# SFD-V1.net
KiCad netlist of a schematic drawn in EAGLE
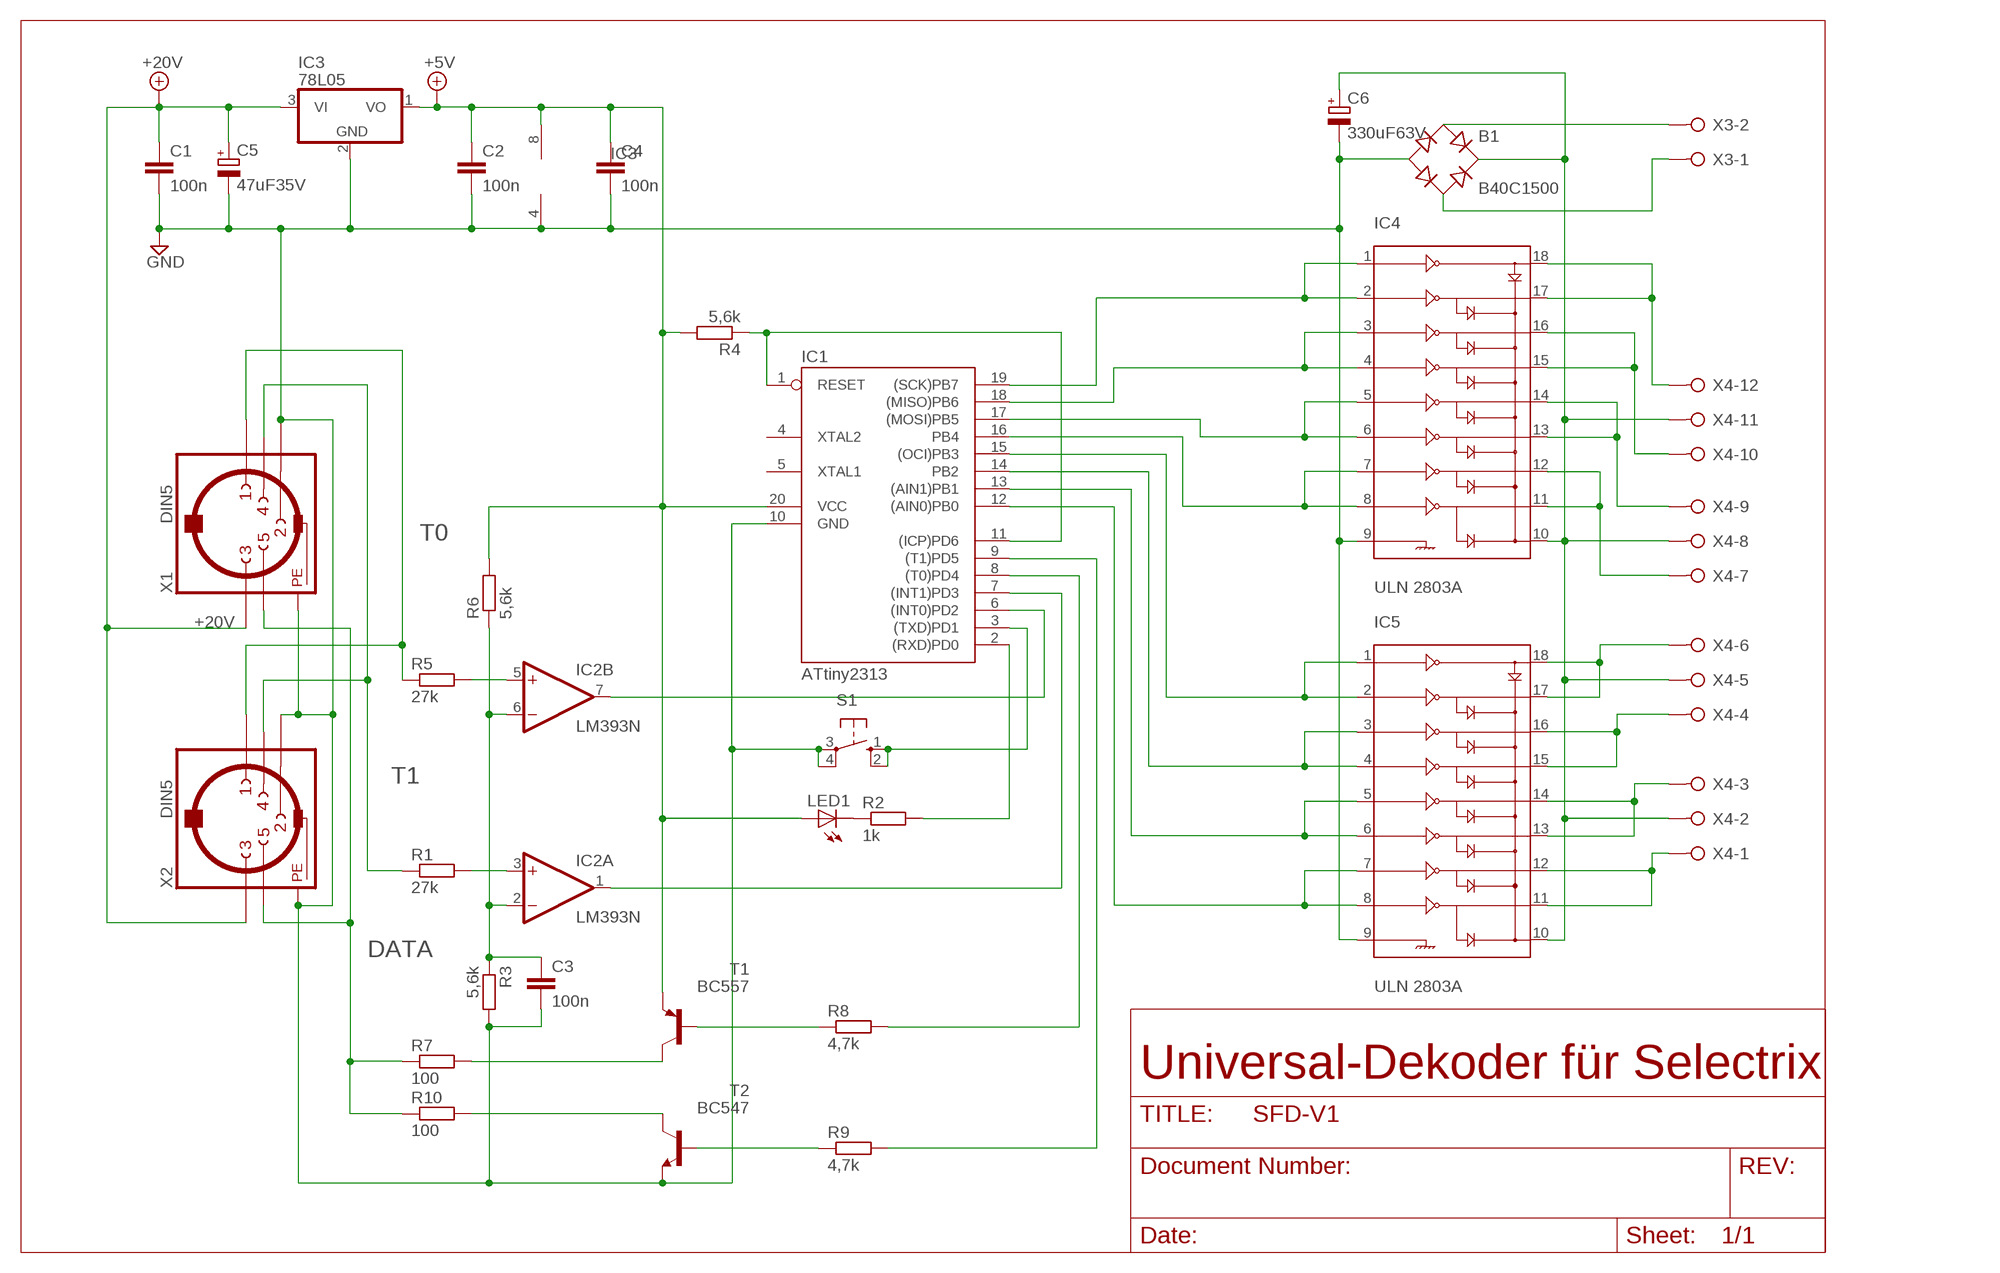
[diagram p0: schematic, sheet 1]

(export (version "E")
  (design (tool "Eeschema 10.0.6"))
  (components
    (comp (ref "B1")
      (value "B40C1500")
      (footprint "eagle-import:RB1A")
      (libsource (lib "eagle-import") (part "RECTIFIER-RB1A"))
    )
    (comp (ref "C1")
      (value "100n")
      (footprint "eagle-import:C025-025X050")
      (libsource (lib "eagle-import") (part "C-EU025-025X050"))
    )
    (comp (ref "C2")
      (value "100n")
      (footprint "eagle-import:C025-025X050")
      (libsource (lib "eagle-import") (part "C-EU025-025X050"))
    )
    (comp (ref "C3")
      (value "100n")
      (footprint "eagle-import:C025-025X050")
      (libsource (lib "eagle-import") (part "C-EU025-025X050"))
    )
    (comp (ref "C4")
      (value "100n")
      (footprint "eagle-import:C025-025X050")
      (libsource (lib "eagle-import") (part "C-EU025-025X050"))
    )
    (comp (ref "C5")
      (value "47uF35V")
      (footprint "eagle-import:E2,5-6E")
      (libsource (lib "eagle-import") (part "CPOL-EUE2,5-6E"))
    )
    (comp (ref "C6")
      (value "330uF63V")
      (footprint "eagle-import:E5-13")
      (libsource (lib "eagle-import") (part "rcl_334_CPOL-EUE5-13"))
    )
    (comp (ref "IC1")
      (value "ATtiny2313")
      (footprint "eagle-import:DIL20")
      (libsource (lib "eagle-import") (part "AT90S2313P"))
    )
    (comp (ref "IC2")
      (value "LM393N")
      (footprint "eagle-import:DIL08")
      (libsource (lib "eagle-import") (part "LM393N"))
    )
    (comp (ref "IC3")
      (value "78L05")
      (footprint "eagle-import:TO92")
      (libsource (lib "eagle-import") (part "78ZL05"))
    )
    (comp (ref "IC4")
      (value "ULN 2803A")
      (footprint "eagle-import:DIL18")
      (libsource (lib "eagle-import") (part "ULN2803"))
    )
    (comp (ref "IC5")
      (value "ULN 2803A")
      (footprint "eagle-import:DIL18")
      (libsource (lib "eagle-import") (part "ULN2803"))
    )
    (comp (ref "LED1")
      (value "LED3MM")
      (footprint "eagle-import:LED3MM")
      (libsource (lib "eagle-import") (part "LED3MM"))
    )
    (comp (ref "R1")
      (value "27k")
      (footprint "eagle-import:0207_10")
      (libsource (lib "eagle-import") (part "R-EU_0207/10"))
    )
    (comp (ref "R2")
      (value "1k")
      (footprint "eagle-import:0207_10")
      (libsource (lib "eagle-import") (part "R-EU_0207/10"))
    )
    (comp (ref "R3")
      (value "5,6k")
      (footprint "eagle-import:0207_10")
      (libsource (lib "eagle-import") (part "R-EU_0207/10"))
    )
    (comp (ref "R4")
      (value "5,6k")
      (footprint "eagle-import:0207_10")
      (libsource (lib "eagle-import") (part "R-EU_0207/10"))
    )
    (comp (ref "R5")
      (value "27k")
      (footprint "eagle-import:0207_10")
      (libsource (lib "eagle-import") (part "R-EU_0207/10"))
    )
    (comp (ref "R6")
      (value "5,6k")
      (footprint "eagle-import:0207_10")
      (libsource (lib "eagle-import") (part "R-EU_0207/10"))
    )
    (comp (ref "R7")
      (value "100")
      (footprint "eagle-import:0207_10")
      (libsource (lib "eagle-import") (part "R-EU_0207/10"))
    )
    (comp (ref "R8")
      (value "4,7k")
      (footprint "eagle-import:0207_10")
      (libsource (lib "eagle-import") (part "R-EU_0207/10"))
    )
    (comp (ref "R9")
      (value "4,7k")
      (footprint "eagle-import:0207_10")
      (libsource (lib "eagle-import") (part "R-EU_0207/10"))
    )
    (comp (ref "R10")
      (value "100")
      (footprint "eagle-import:0207_10")
      (libsource (lib "eagle-import") (part "R-EU_0207/10"))
    )
    (comp (ref "S1")
      (value "10-XX")
      (footprint "eagle-import:B3F-10XX")
      (fields (field (name "MPN") "B3F-1000"))
      (libsource (lib "eagle-import") (part "10-XX"))
    )
    (comp (ref "T1")
      (value "BC557")
      (footprint "eagle-import:TO92")
      (libsource (lib "eagle-import") (part "BC557"))
    )
    (comp (ref "T2")
      (value "BC547")
      (footprint "eagle-import:TO92")
      (libsource (lib "eagle-import") (part "BC547"))
    )
    (comp (ref "X1")
      (value "DIN5")
      (footprint "eagle-import:CON-HIRSCHMANN_DIN5")
      (libsource (lib "eagle-import") (part "CON-HIRSCHMANN_DIN5"))
    )
    (comp (ref "X2")
      (value "DIN5")
      (footprint "eagle-import:CON-HIRSCHMANN_DIN5")
      (libsource (lib "eagle-import") (part "CON-HIRSCHMANN_DIN5"))
    )
    (comp (ref "X3")
      (value "W237-02P")
      (footprint "eagle-import:W237-132")
      (libsource (lib "eagle-import") (part "W237-02P"))
    )
    (comp (ref "X4")
      (value "W237-12P")
      (footprint "eagle-import:W237-12P")
      (libsource (lib "eagle-import") (part "W237-12P"))
    )
  )
  (nets
    (net (code "1") (name "+5V") (class "Default")
      (node (ref "C2") (pin "1") (pinfunction "1_1") (pintype "passive"))
      (node (ref "C4") (pin "1") (pinfunction "1_1") (pintype "passive"))
      (node (ref "IC1") (pin "20") (pinfunction "VCC_20") (pintype "power_in"))
      (node (ref "IC2") (pin "8") (pinfunction "V+_8") (pintype "power_in"))
      (node (ref "IC3") (pin "1") (pinfunction "VO_1") (pintype "passive"))
      (node (ref "LED1") (pin "A") (pinfunction "A_A") (pintype "passive"))
      (node (ref "R4") (pin "2") (pinfunction "2_2") (pintype "passive"))
      (node (ref "R6") (pin "2") (pinfunction "2_2") (pintype "passive"))
      (node (ref "T1") (pin "1") (pinfunction "E_1") (pintype "passive"))
    )
    (net (code "2") (name "+20V") (class "Default")
      (node (ref "C1") (pin "1") (pinfunction "1_1") (pintype "passive"))
      (node (ref "C5") (pin "+") (pinfunction "+_+") (pintype "passive"))
      (node (ref "IC3") (pin "3") (pinfunction "VI_3") (pintype "input"))
      (node (ref "X1") (pin "3") (pinfunction "3_3") (pintype "passive"))
      (node (ref "X2") (pin "3") (pinfunction "3_3") (pintype "passive"))
    )
    (net (code "3") (name "/DATA") (class "Default")
      (node (ref "R10") (pin "1") (pinfunction "1_1") (pintype "passive"))
      (node (ref "R7") (pin "1") (pinfunction "1_1") (pintype "passive"))
      (node (ref "X1") (pin "5") (pinfunction "5_5") (pintype "passive"))
      (node (ref "X2") (pin "5") (pinfunction "5_5") (pintype "passive"))
    )
    (net (code "4") (name "/T0") (class "Default")
      (node (ref "R5") (pin "1") (pinfunction "1_1") (pintype "passive"))
      (node (ref "X1") (pin "1") (pinfunction "1_1") (pintype "passive"))
      (node (ref "X2") (pin "1") (pinfunction "1_1") (pintype "passive"))
    )
    (net (code "5") (name "/T1") (class "Default")
      (node (ref "R1") (pin "1") (pinfunction "1_1") (pintype "passive"))
      (node (ref "X1") (pin "4") (pinfunction "4_4") (pintype "passive"))
      (node (ref "X2") (pin "4") (pinfunction "4_4") (pintype "passive"))
    )
    (net (code "6") (name "GND") (class "Default")
      (node (ref "B1") (pin "-") (pinfunction "-_-") (pintype "passive"))
      (node (ref "C1") (pin "2") (pinfunction "2_2") (pintype "passive"))
      (node (ref "C2") (pin "2") (pinfunction "2_2") (pintype "passive"))
      (node (ref "C3") (pin "2") (pinfunction "2_2") (pintype "passive"))
      (node (ref "C4") (pin "2") (pinfunction "2_2") (pintype "passive"))
      (node (ref "C5") (pin "-") (pinfunction "-_-") (pintype "passive"))
      (node (ref "C6") (pin "-") (pinfunction "-_-") (pintype "passive"))
      (node (ref "IC1") (pin "10") (pinfunction "GND_10") (pintype "power_in"))
      (node (ref "IC2") (pin "4") (pinfunction "V-_4") (pintype "power_in"))
      (node (ref "IC3") (pin "2") (pinfunction "GND_2") (pintype "passive"))
      (node (ref "IC4") (pin "9") (pinfunction "9_9") (pintype "bidirectional"))
      (node (ref "IC5") (pin "9") (pinfunction "9_9") (pintype "bidirectional"))
      (node (ref "R3") (pin "2") (pinfunction "2_2") (pintype "passive"))
      (node (ref "S1") (pin "3") (pinfunction "P_3") (pintype "passive"))
      (node (ref "S1") (pin "4") (pinfunction "P1_4") (pintype "passive"))
      (node (ref "T2") (pin "1") (pinfunction "E_1") (pintype "passive"))
      (node (ref "X1") (pin "2") (pinfunction "2_2") (pintype "passive"))
      (node (ref "X1") (pin "PE") (pinfunction "PE_PE") (pintype "power_in"))
      (node (ref "X1") (pin "PE1") (pinfunction "PE_PE1") (pintype "power_in"))
      (node (ref "X1") (pin "PE@") (pinfunction "PE_PE@") (pintype "power_in"))
      (node (ref "X1") (pin "PE@1") (pinfunction "PE_PE@1") (pintype "power_in"))
      (node (ref "X2") (pin "2") (pinfunction "2_2") (pintype "passive"))
      (node (ref "X2") (pin "PE") (pinfunction "PE_PE") (pintype "power_in"))
      (node (ref "X2") (pin "PE1") (pinfunction "PE_PE1") (pintype "power_in"))
      (node (ref "X2") (pin "PE@") (pinfunction "PE_PE@") (pintype "power_in"))
      (node (ref "X2") (pin "PE@1") (pinfunction "PE_PE@1") (pintype "power_in"))
    )
    (net (code "7") (name "Net-(IC1-(AIN0)PB0)") (class "Default")
      (node (ref "IC1") (pin "12") (pinfunction "(AIN0)PB0_12") (pintype "bidirectional"))
      (node (ref "IC5") (pin "7") (pinfunction "7_7") (pintype "bidirectional"))
      (node (ref "IC5") (pin "8") (pinfunction "8_8") (pintype "bidirectional"))
    )
    (net (code "8") (name "Net-(IC1-(AIN1)PB1)") (class "Default")
      (node (ref "IC1") (pin "13") (pinfunction "(AIN1)PB1_13") (pintype "bidirectional"))
      (node (ref "IC5") (pin "5") (pinfunction "5_5") (pintype "bidirectional"))
      (node (ref "IC5") (pin "6") (pinfunction "6_6") (pintype "bidirectional"))
    )
    (net (code "9") (name "Net-(IC1-(ICP)PD6)") (class "Default")
      (node (ref "IC1") (pin "1") (pinfunction "RESET_1") (pintype "bidirectional"))
      (node (ref "IC1") (pin "11") (pinfunction "(ICP)PD6_11") (pintype "bidirectional"))
      (node (ref "R4") (pin "1") (pinfunction "1_1") (pintype "passive"))
    )
    (net (code "10") (name "Net-(IC1-(INT0)PD2)") (class "Default")
      (node (ref "IC1") (pin "6") (pinfunction "(INT0)PD2_6") (pintype "bidirectional"))
      (node (ref "IC2") (pin "7") (pinfunction "OUT_7") (pintype "output"))
    )
    (net (code "11") (name "Net-(IC1-(INT1)PD3)") (class "Default")
      (node (ref "IC1") (pin "7") (pinfunction "(INT1)PD3_7") (pintype "bidirectional"))
      (node (ref "IC2") (pin "1") (pinfunction "OUT_1") (pintype "output"))
    )
    (net (code "12") (name "Net-(IC1-(MISO)PB6)") (class "Default")
      (node (ref "IC1") (pin "18") (pinfunction "(MISO)PB6_18") (pintype "bidirectional"))
      (node (ref "IC4") (pin "3") (pinfunction "3_3") (pintype "bidirectional"))
      (node (ref "IC4") (pin "4") (pinfunction "4_4") (pintype "bidirectional"))
    )
    (net (code "13") (name "Net-(IC1-(MOSI)PB5)") (class "Default")
      (node (ref "IC1") (pin "17") (pinfunction "(MOSI)PB5_17") (pintype "bidirectional"))
      (node (ref "IC4") (pin "5") (pinfunction "5_5") (pintype "bidirectional"))
      (node (ref "IC4") (pin "6") (pinfunction "6_6") (pintype "bidirectional"))
    )
    (net (code "14") (name "Net-(IC1-(OCI)PB3)") (class "Default")
      (node (ref "IC1") (pin "15") (pinfunction "(OCI)PB3_15") (pintype "bidirectional"))
      (node (ref "IC5") (pin "1") (pinfunction "1_1") (pintype "bidirectional"))
      (node (ref "IC5") (pin "2") (pinfunction "2_2") (pintype "bidirectional"))
    )
    (net (code "15") (name "Net-(IC1-(RXD)PD0)") (class "Default")
      (node (ref "IC1") (pin "2") (pinfunction "(RXD)PD0_2") (pintype "bidirectional"))
      (node (ref "R2") (pin "2") (pinfunction "2_2") (pintype "passive"))
    )
    (net (code "16") (name "Net-(IC1-(SCK)PB7)") (class "Default")
      (node (ref "IC1") (pin "19") (pinfunction "(SCK)PB7_19") (pintype "bidirectional"))
      (node (ref "IC4") (pin "1") (pinfunction "1_1") (pintype "bidirectional"))
      (node (ref "IC4") (pin "2") (pinfunction "2_2") (pintype "bidirectional"))
    )
    (net (code "17") (name "Net-(IC1-(T0)PD4)") (class "Default")
      (node (ref "IC1") (pin "8") (pinfunction "(T0)PD4_8") (pintype "bidirectional"))
      (node (ref "R8") (pin "2") (pinfunction "2_2") (pintype "passive"))
    )
    (net (code "18") (name "Net-(IC1-(T1)PD5)") (class "Default")
      (node (ref "IC1") (pin "9") (pinfunction "(T1)PD5_9") (pintype "bidirectional"))
      (node (ref "R9") (pin "2") (pinfunction "2_2") (pintype "passive"))
    )
    (net (code "19") (name "Net-(IC1-(TXD)PD1)") (class "Default")
      (node (ref "IC1") (pin "3") (pinfunction "(TXD)PD1_3") (pintype "bidirectional"))
      (node (ref "S1") (pin "1") (pinfunction "S_1") (pintype "passive"))
      (node (ref "S1") (pin "2") (pinfunction "S1_2") (pintype "passive"))
    )
    (net (code "20") (name "Net-(IC1-PB2)") (class "Default")
      (node (ref "IC1") (pin "14") (pinfunction "PB2_14") (pintype "bidirectional"))
      (node (ref "IC5") (pin "3") (pinfunction "3_3") (pintype "bidirectional"))
      (node (ref "IC5") (pin "4") (pinfunction "4_4") (pintype "bidirectional"))
    )
    (net (code "21") (name "Net-(IC1-PB4)") (class "Default")
      (node (ref "IC1") (pin "16") (pinfunction "PB4_16") (pintype "bidirectional"))
      (node (ref "IC4") (pin "7") (pinfunction "7_7") (pintype "bidirectional"))
      (node (ref "IC4") (pin "8") (pinfunction "8_8") (pintype "bidirectional"))
    )
    (net (code "22") (name "Net-(IC2A-+IN)") (class "Default")
      (node (ref "IC2") (pin "3") (pinfunction "+IN_3") (pintype "input"))
      (node (ref "R1") (pin "2") (pinfunction "2_2") (pintype "passive"))
    )
    (net (code "23") (name "Net-(IC2A--IN)") (class "Default")
      (node (ref "C3") (pin "1") (pinfunction "1_1") (pintype "passive"))
      (node (ref "IC2") (pin "2") (pinfunction "-IN_2") (pintype "input"))
      (node (ref "IC2") (pin "6") (pinfunction "-IN_6") (pintype "input"))
      (node (ref "R3") (pin "1") (pinfunction "1_1") (pintype "passive"))
      (node (ref "R6") (pin "1") (pinfunction "1_1") (pintype "passive"))
    )
    (net (code "24") (name "Net-(IC2B-+IN)") (class "Default")
      (node (ref "IC2") (pin "5") (pinfunction "+IN_5") (pintype "input"))
      (node (ref "R5") (pin "2") (pinfunction "2_2") (pintype "passive"))
    )
    (net (code "25") (name "Net-(LED1-C)") (class "Default")
      (node (ref "LED1") (pin "K") (pinfunction "C_K") (pintype "passive"))
      (node (ref "R2") (pin "1") (pinfunction "1_1") (pintype "passive"))
    )
    (net (code "26") (name "Net-(T1-B)") (class "Default")
      (node (ref "R8") (pin "1") (pinfunction "1_1") (pintype "passive"))
      (node (ref "T1") (pin "2") (pinfunction "B_2") (pintype "passive"))
    )
    (net (code "27") (name "Net-(T1-C)") (class "Default")
      (node (ref "R7") (pin "2") (pinfunction "2_2") (pintype "passive"))
      (node (ref "T1") (pin "3") (pinfunction "C_3") (pintype "passive"))
    )
    (net (code "28") (name "Net-(T2-B)") (class "Default")
      (node (ref "R9") (pin "1") (pinfunction "1_1") (pintype "passive"))
      (node (ref "T2") (pin "2") (pinfunction "B_2") (pintype "passive"))
    )
    (net (code "29") (name "Net-(T2-C)") (class "Default")
      (node (ref "R10") (pin "2") (pinfunction "2_2") (pintype "passive"))
      (node (ref "T2") (pin "3") (pinfunction "C_3") (pintype "passive"))
    )
    (net (code "30") (name "Net-(X3A-KL)") (class "Default")
      (node (ref "B1") (pin "AC2") (pinfunction "AC2_AC2") (pintype "passive"))
      (node (ref "X3") (pin "1") (pinfunction "KL_1") (pintype "passive"))
    )
    (net (code "31") (name "Net-(X3B-KL)") (class "Default")
      (node (ref "B1") (pin "AC1") (pinfunction "AC1_AC1") (pintype "passive"))
      (node (ref "X3") (pin "2") (pinfunction "KL_2") (pintype "passive"))
    )
    (net (code "32") (name "Net-(X4A-KL)") (class "Default")
      (node (ref "IC5") (pin "11") (pinfunction "11_11") (pintype "bidirectional"))
      (node (ref "IC5") (pin "12") (pinfunction "12_12") (pintype "bidirectional"))
      (node (ref "X4") (pin "1") (pinfunction "KL_1") (pintype "passive"))
    )
    (net (code "33") (name "Net-(X4B-KL)") (class "Default")
      (node (ref "IC4") (pin "15") (pinfunction "15_15") (pintype "bidirectional"))
      (node (ref "IC4") (pin "16") (pinfunction "16_16") (pintype "bidirectional"))
      (node (ref "X4") (pin "10") (pinfunction "KL_10") (pintype "passive"))
    )
    (net (code "34") (name "Net-(X4C-KL)") (class "Default")
      (node (ref "B1") (pin "+") (pinfunction "+_+") (pintype "passive"))
      (node (ref "C6") (pin "+") (pinfunction "+_+") (pintype "passive"))
      (node (ref "IC4") (pin "10") (pinfunction "10_10") (pintype "bidirectional"))
      (node (ref "IC5") (pin "10") (pinfunction "10_10") (pintype "bidirectional"))
      (node (ref "X4") (pin "11") (pinfunction "KL_11") (pintype "passive"))
      (node (ref "X4") (pin "2") (pinfunction "KL_2") (pintype "passive"))
      (node (ref "X4") (pin "5") (pinfunction "KL_5") (pintype "passive"))
      (node (ref "X4") (pin "8") (pinfunction "KL_8") (pintype "passive"))
    )
    (net (code "35") (name "Net-(X4D-KL)") (class "Default")
      (node (ref "IC4") (pin "17") (pinfunction "17_17") (pintype "bidirectional"))
      (node (ref "IC4") (pin "18") (pinfunction "18_18") (pintype "bidirectional"))
      (node (ref "X4") (pin "12") (pinfunction "KL_12") (pintype "passive"))
    )
    (net (code "36") (name "Net-(X4F-KL)") (class "Default")
      (node (ref "IC5") (pin "13") (pinfunction "13_13") (pintype "bidirectional"))
      (node (ref "IC5") (pin "14") (pinfunction "14_14") (pintype "bidirectional"))
      (node (ref "X4") (pin "3") (pinfunction "KL_3") (pintype "passive"))
    )
    (net (code "37") (name "Net-(X4G-KL)") (class "Default")
      (node (ref "IC5") (pin "15") (pinfunction "15_15") (pintype "bidirectional"))
      (node (ref "IC5") (pin "16") (pinfunction "16_16") (pintype "bidirectional"))
      (node (ref "X4") (pin "4") (pinfunction "KL_4") (pintype "passive"))
    )
    (net (code "38") (name "Net-(X4I-KL)") (class "Default")
      (node (ref "IC5") (pin "17") (pinfunction "17_17") (pintype "bidirectional"))
      (node (ref "IC5") (pin "18") (pinfunction "18_18") (pintype "bidirectional"))
      (node (ref "X4") (pin "6") (pinfunction "KL_6") (pintype "passive"))
    )
    (net (code "39") (name "Net-(X4J-KL)") (class "Default")
      (node (ref "IC4") (pin "11") (pinfunction "11_11") (pintype "bidirectional"))
      (node (ref "IC4") (pin "12") (pinfunction "12_12") (pintype "bidirectional"))
      (node (ref "X4") (pin "7") (pinfunction "KL_7") (pintype "passive"))
    )
    (net (code "40") (name "Net-(X4L-KL)") (class "Default")
      (node (ref "IC4") (pin "13") (pinfunction "13_13") (pintype "bidirectional"))
      (node (ref "IC4") (pin "14") (pinfunction "14_14") (pintype "bidirectional"))
      (node (ref "X4") (pin "9") (pinfunction "KL_9") (pintype "passive"))
    )
    (net (code "41") (name "unconnected-(IC1-XTAL1-Pad5)") (class "Default")
      (node (ref "IC1") (pin "5") (pinfunction "XTAL1_5") (pintype "bidirectional"))
    )
    (net (code "42") (name "unconnected-(IC1-XTAL2-Pad4)") (class "Default")
      (node (ref "IC1") (pin "4") (pinfunction "XTAL2_4") (pintype "bidirectional"))
    )
  )
)
